# adapter1.net
KiCad netlist of a schematic drawn in EAGLE
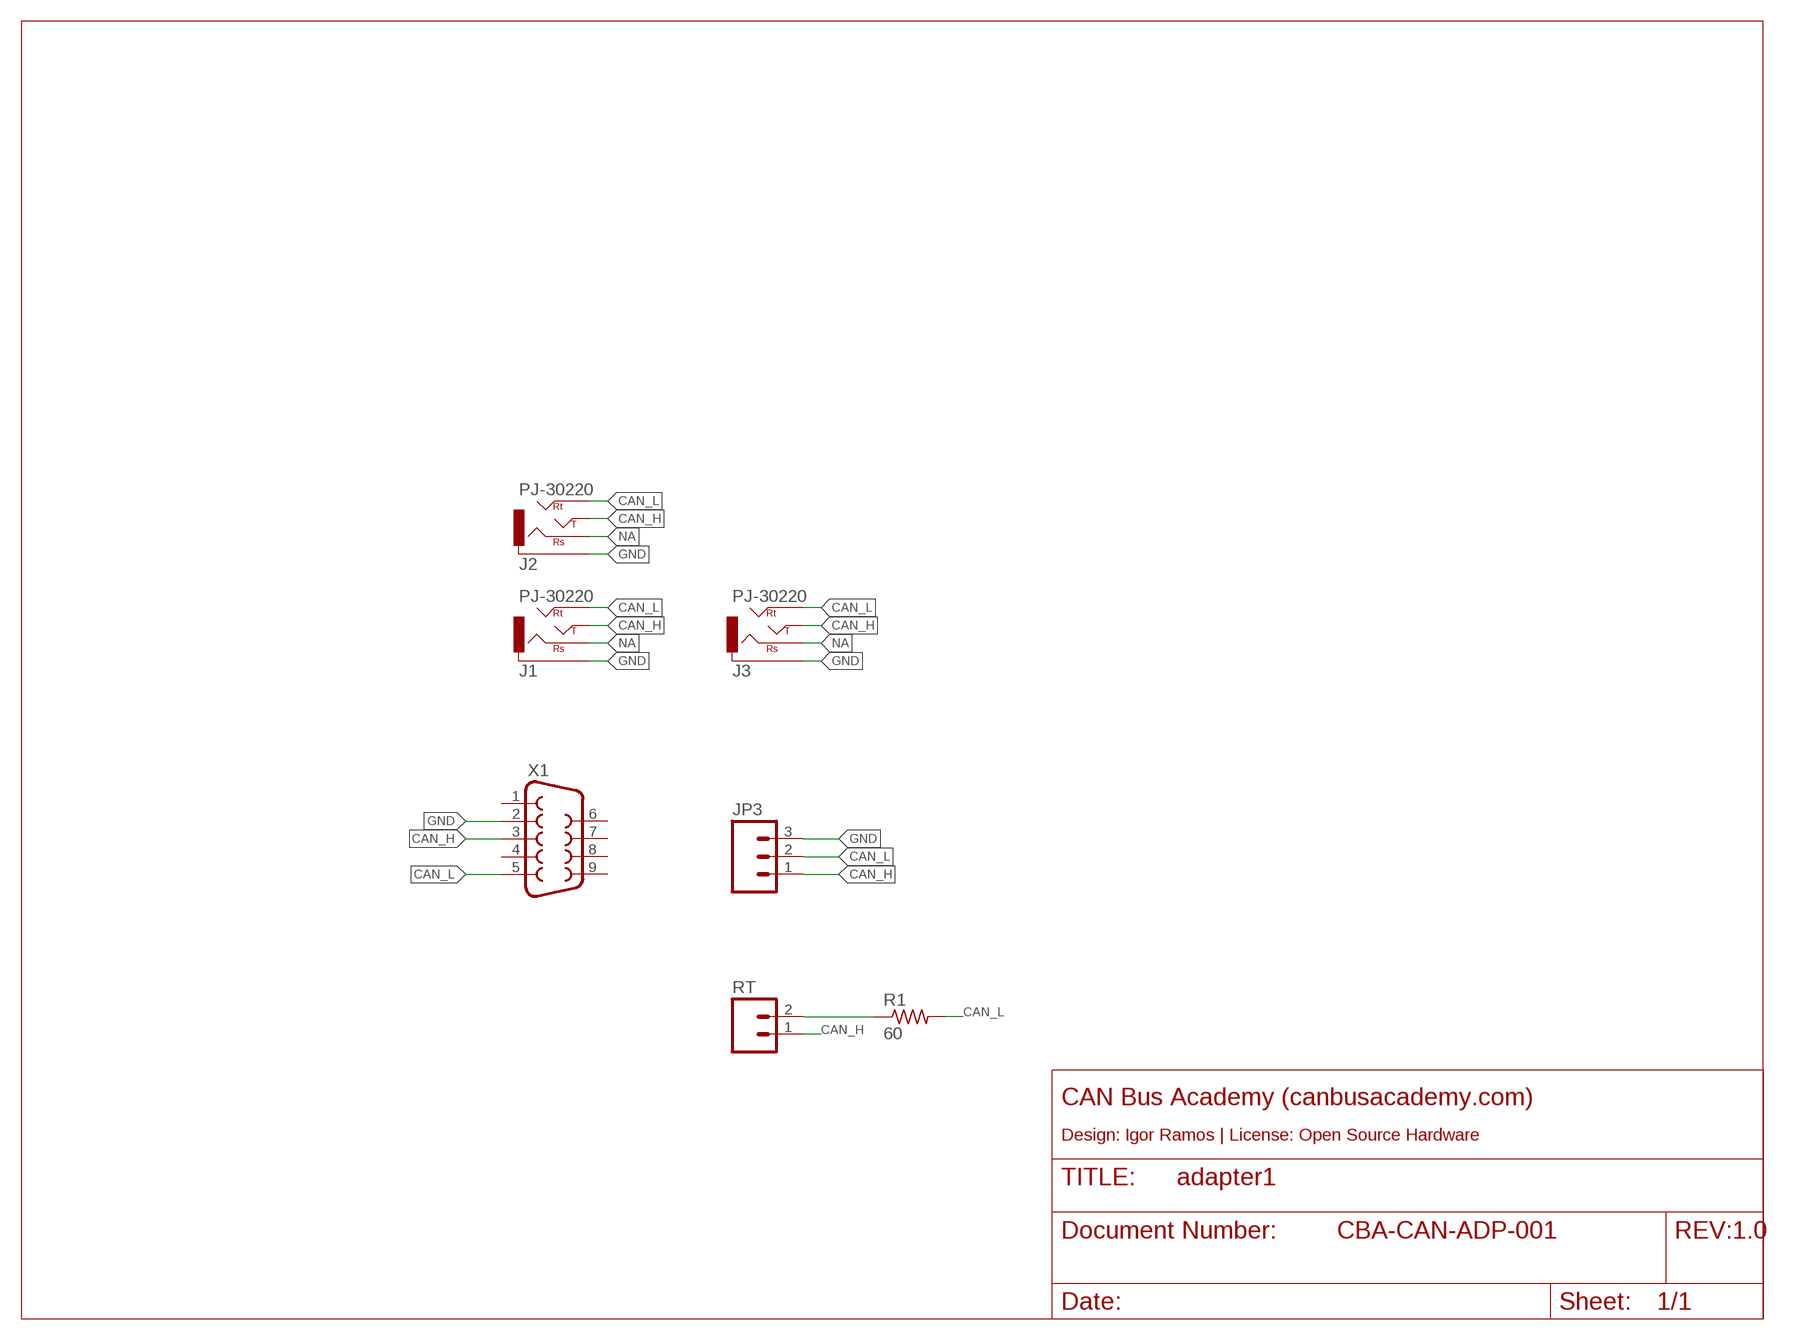
[diagram p0: schematic, sheet 1]

(export (version "E")
  (design (tool "Eeschema 10.0.6"))
  (components
    (comp (ref "J1")
      (value "PJ-30220")
      (footprint "eagle-import:PJ-30220")
      (fields (field (name "PARTNO") "PJ30220"))
      (libsource (lib "eagle-import") (part "AUDIO_JACK_4POSA"))
    )
    (comp (ref "J2")
      (value "PJ-30220")
      (footprint "eagle-import:PJ-30220")
      (fields (field (name "PARTNO") "PJ30220"))
      (libsource (lib "eagle-import") (part "AUDIO_JACK_4POSA"))
    )
    (comp (ref "J3")
      (value "PJ-30220")
      (footprint "eagle-import:PJ-30220")
      (fields (field (name "PARTNO") "PJ30220"))
      (libsource (lib "eagle-import") (part "AUDIO_JACK_4POSA"))
    )
    (comp (ref "JP3")
      (value "M03PTH")
      (footprint "eagle-import:1X03")
      (libsource (lib "eagle-import") (part "M03PTH"))
    )
    (comp (ref "R1")
      (value "60")
      (footprint "eagle-import:M0805")
      (libsource (lib "eagle-import") (part "R-US_M0805"))
    )
    (comp (ref "RT")
      (value "M02PTH")
      (footprint "eagle-import:1X02")
      (libsource (lib "eagle-import") (part "M02PTH"))
    )
    (comp (ref "X1")
      (value "DB9FEMALE")
      (footprint "eagle-import:DB9")
      (libsource (lib "eagle-import") (part "DB9FEMALE"))
    )
  )
  (nets
    (net (code "1") (name "CAN_H") (class "Default")
      (node (ref "J1") (pin "P$03") (pinfunction "TIP_P$03") (pintype "bidirectional"))
      (node (ref "J1") (pin "P$03B") (pinfunction "TIP_P$03B") (pintype "bidirectional"))
      (node (ref "J2") (pin "P$03") (pinfunction "TIP_P$03") (pintype "bidirectional"))
      (node (ref "J2") (pin "P$03B") (pinfunction "TIP_P$03B") (pintype "bidirectional"))
      (node (ref "J3") (pin "P$03") (pinfunction "TIP_P$03") (pintype "bidirectional"))
      (node (ref "J3") (pin "P$03B") (pinfunction "TIP_P$03B") (pintype "bidirectional"))
      (node (ref "JP3") (pin "1") (pinfunction "1_1") (pintype "passive"))
      (node (ref "RT") (pin "1") (pinfunction "1_1") (pintype "passive"))
      (node (ref "X1") (pin "3") (pinfunction "3_3") (pintype "passive"))
    )
    (net (code "2") (name "CAN_L") (class "Default")
      (node (ref "J1") (pin "P$04") (pinfunction "RT_P$04") (pintype "bidirectional"))
      (node (ref "J2") (pin "P$04") (pinfunction "RT_P$04") (pintype "bidirectional"))
      (node (ref "J3") (pin "P$04") (pinfunction "RT_P$04") (pintype "bidirectional"))
      (node (ref "JP3") (pin "2") (pinfunction "2_2") (pintype "passive"))
      (node (ref "R1") (pin "2") (pinfunction "2_2") (pintype "passive"))
      (node (ref "X1") (pin "5") (pinfunction "5_5") (pintype "passive"))
    )
    (net (code "3") (name "GND") (class "Default")
      (node (ref "J1") (pin "P$01") (pinfunction "SLEEVE_P$01") (pintype "bidirectional"))
      (node (ref "J2") (pin "P$01") (pinfunction "SLEEVE_P$01") (pintype "bidirectional"))
      (node (ref "J3") (pin "P$01") (pinfunction "SLEEVE_P$01") (pintype "bidirectional"))
      (node (ref "JP3") (pin "3") (pinfunction "3_3") (pintype "passive"))
      (node (ref "X1") (pin "2") (pinfunction "2_2") (pintype "passive"))
    )
    (net (code "4") (name "NA") (class "Default")
      (node (ref "J1") (pin "P$02") (pinfunction "RS_P$02") (pintype "bidirectional"))
      (node (ref "J2") (pin "P$02") (pinfunction "RS_P$02") (pintype "bidirectional"))
      (node (ref "J3") (pin "P$02") (pinfunction "RS_P$02") (pintype "bidirectional"))
    )
    (net (code "5") (name "Net-(R1-Pad1)") (class "Default")
      (node (ref "R1") (pin "1") (pinfunction "1_1") (pintype "passive"))
      (node (ref "RT") (pin "2") (pinfunction "2_2") (pintype "passive"))
    )
    (net (code "6") (name "unconnected-(X1-Pad1)") (class "Default")
      (node (ref "X1") (pin "1") (pinfunction "1_1") (pintype "passive"))
    )
    (net (code "7") (name "unconnected-(X1-Pad4)") (class "Default")
      (node (ref "X1") (pin "4") (pinfunction "4_4") (pintype "passive"))
    )
    (net (code "8") (name "unconnected-(X1-Pad6)") (class "Default")
      (node (ref "X1") (pin "6") (pinfunction "6_6") (pintype "passive"))
    )
    (net (code "9") (name "unconnected-(X1-Pad7)") (class "Default")
      (node (ref "X1") (pin "7") (pinfunction "7_7") (pintype "passive"))
    )
    (net (code "10") (name "unconnected-(X1-Pad8)") (class "Default")
      (node (ref "X1") (pin "8") (pinfunction "8_8") (pintype "passive"))
    )
    (net (code "11") (name "unconnected-(X1-Pad9)") (class "Default")
      (node (ref "X1") (pin "9") (pinfunction "9_9") (pintype "passive"))
    )
  )
)
